# The_X_Project.net
KiCad netlist of a schematic drawn in EAGLE
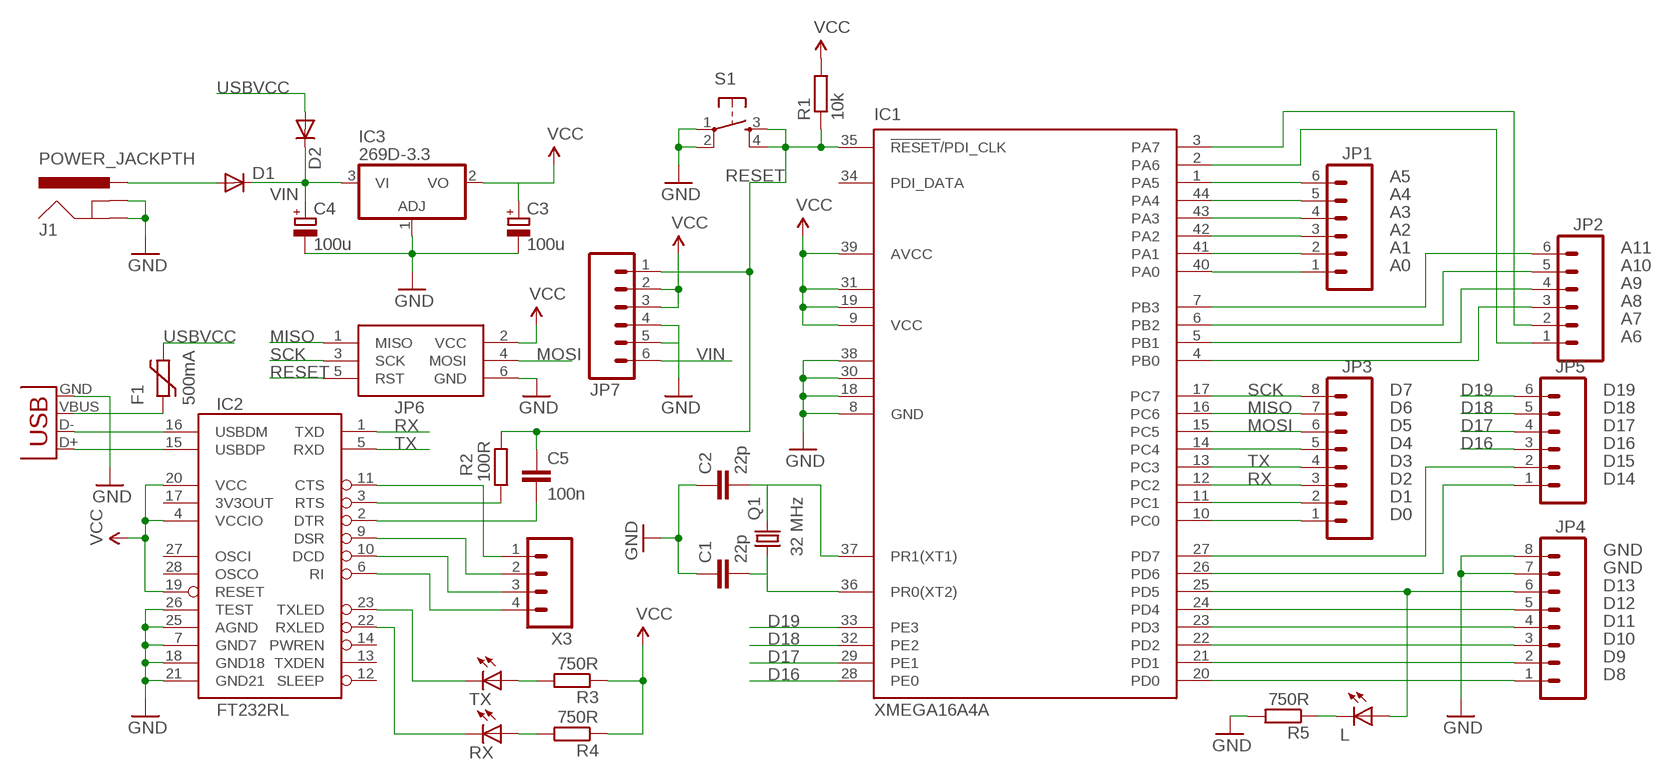
[diagram p0: schematic, sheet 1]

(export (version "E")
  (design (tool "Eeschema 10.0.6"))
  (components
    (comp (ref "C1")
      (value "22p")
      (footprint "eagle-import:C0805")
      (libsource (lib "eagle-import") (part "C-EUC0805"))
    )
    (comp (ref "C2")
      (value "22p")
      (footprint "eagle-import:C0805")
      (libsource (lib "eagle-import") (part "C-EUC0805"))
    )
    (comp (ref "C3")
      (value "100u")
      (footprint "eagle-import:PANASONIC_D")
      (libsource (lib "eagle-import") (part "CPOL-EUD"))
    )
    (comp (ref "C4")
      (value "100u")
      (footprint "eagle-import:PANASONIC_D")
      (libsource (lib "eagle-import") (part "CPOL-EUD"))
    )
    (comp (ref "C5")
      (value "100n")
      (footprint "eagle-import:C0805")
      (libsource (lib "eagle-import") (part "C-EUC0805"))
    )
    (comp (ref "D1")
      (value "DIODE-SMB")
      (footprint "eagle-import:SMB")
      (libsource (lib "eagle-import") (part "DIODE-SMB"))
    )
    (comp (ref "D2")
      (value "DIODE-SMB")
      (footprint "eagle-import:SMB")
      (libsource (lib "eagle-import") (part "DIODE-SMB"))
    )
    (comp (ref "F1")
      (value "500mA")
      (footprint "eagle-import:1812L")
      (libsource (lib "eagle-import") (part "1812L"))
    )
    (comp (ref "IC1")
      (value "XMEGA16A4A")
      (footprint "eagle-import:TQFP44")
      (libsource (lib "eagle-import") (part "XMEGA16A4A"))
    )
    (comp (ref "IC2")
      (value "FT232RL")
      (footprint "eagle-import:SSOP28DB")
      (libsource (lib "eagle-import") (part "FT232RLSSOP"))
    )
    (comp (ref "IC3")
      (value "269D-3.3")
      (footprint "eagle-import:DPACK")
      (libsource (lib "eagle-import") (part "MC33269?D-3.3"))
    )
    (comp (ref "J1")
      (value "POWER_JACKPTH")
      (footprint "eagle-import:POWER_JACK_PTH")
      (libsource (lib "eagle-import") (part "POWER_JACKPTH"))
    )
    (comp (ref "JP1")
      (value "M06SIP")
      (footprint "eagle-import:1X06")
      (libsource (lib "eagle-import") (part "M06SIP"))
    )
    (comp (ref "JP2")
      (value "M06SIP")
      (footprint "eagle-import:1X06")
      (libsource (lib "eagle-import") (part "M06SIP"))
    )
    (comp (ref "JP3")
      (value "M08")
      (footprint "eagle-import:1X08")
      (libsource (lib "eagle-import") (part "M08"))
    )
    (comp (ref "JP4")
      (value "M08")
      (footprint "eagle-import:1X08")
      (libsource (lib "eagle-import") (part "M08"))
    )
    (comp (ref "JP5")
      (value "M06SIP")
      (footprint "eagle-import:1X06")
      (libsource (lib "eagle-import") (part "M06SIP"))
    )
    (comp (ref "JP6")
      (value "AVRISP-6")
      (footprint "eagle-import:AVRISP")
      (libsource (lib "eagle-import") (part "AVRISP-6"))
    )
    (comp (ref "JP7")
      (value "M06SIP")
      (footprint "eagle-import:1X06")
      (libsource (lib "eagle-import") (part "M06SIP"))
    )
    (comp (ref "L")
      (value "LED1206")
      (footprint "eagle-import:LED-1206")
      (libsource (lib "eagle-import") (part "LED1206"))
    )
    (comp (ref "Q1")
      (value "32 MHz")
      (footprint "eagle-import:HC49U-LM")
      (libsource (lib "eagle-import") (part "CRYSTALHC49U-LM"))
    )
    (comp (ref "R1")
      (value "10k")
      (footprint "eagle-import:R0805")
      (libsource (lib "eagle-import") (part "R-EU_R0805"))
    )
    (comp (ref "R2")
      (value "100R")
      (footprint "eagle-import:R0805")
      (libsource (lib "eagle-import") (part "R-EU_R0805"))
    )
    (comp (ref "R3")
      (value "750R")
      (footprint "eagle-import:R0805")
      (libsource (lib "eagle-import") (part "R-EU_R0805"))
    )
    (comp (ref "R4")
      (value "750R")
      (footprint "eagle-import:R0805")
      (libsource (lib "eagle-import") (part "R-EU_R0805"))
    )
    (comp (ref "R5")
      (value "750R")
      (footprint "eagle-import:R0805")
      (libsource (lib "eagle-import") (part "R-EU_R0805"))
    )
    (comp (ref "RX")
      (value "LED1206")
      (footprint "eagle-import:LED-1206")
      (libsource (lib "eagle-import") (part "LED1206"))
    )
    (comp (ref "S1")
      (value "TAC_SWITCHPTH")
      (footprint "eagle-import:TACTILE-PTH")
      (libsource (lib "eagle-import") (part "TAC_SWITCHPTH"))
    )
    (comp (ref "TX")
      (value "LED1206")
      (footprint "eagle-import:LED-1206")
      (libsource (lib "eagle-import") (part "LED1206"))
    )
    (comp (ref "X1")
      (value "USBSMD")
      (footprint "eagle-import:USB-MINIB")
      (libsource (lib "eagle-import") (part "USBSMD"))
    )
    (comp (ref "X3")
      (value "M04PTH")
      (footprint "eagle-import:1X04")
      (libsource (lib "eagle-import") (part "M04PTH"))
    )
  )
  (nets
    (net (code "1") (name "/D16") (class "Default")
      (node (ref "IC1") (pin "28") (pinfunction "PE0_28") (pintype "bidirectional"))
      (node (ref "JP5") (pin "3") (pinfunction "3_3") (pintype "passive"))
    )
    (net (code "2") (name "/D17") (class "Default")
      (node (ref "IC1") (pin "29") (pinfunction "PE1_29") (pintype "bidirectional"))
      (node (ref "JP5") (pin "4") (pinfunction "4_4") (pintype "passive"))
    )
    (net (code "3") (name "/D18") (class "Default")
      (node (ref "IC1") (pin "32") (pinfunction "PE2_32") (pintype "bidirectional"))
      (node (ref "JP5") (pin "5") (pinfunction "5_5") (pintype "passive"))
    )
    (net (code "4") (name "/D19") (class "Default")
      (node (ref "IC1") (pin "33") (pinfunction "PE3_33") (pintype "bidirectional"))
      (node (ref "JP5") (pin "6") (pinfunction "6_6") (pintype "passive"))
    )
    (net (code "5") (name "/MISO") (class "Default")
      (node (ref "IC1") (pin "16") (pinfunction "PC6_16") (pintype "bidirectional"))
      (node (ref "JP3") (pin "7") (pinfunction "7_7") (pintype "passive"))
      (node (ref "JP6") (pin "1") (pinfunction "MISO_1") (pintype "input"))
    )
    (net (code "6") (name "/MOSI") (class "Default")
      (node (ref "IC1") (pin "15") (pinfunction "PC5_15") (pintype "bidirectional"))
      (node (ref "JP3") (pin "6") (pinfunction "6_6") (pintype "passive"))
      (node (ref "JP6") (pin "4") (pinfunction "MOSI_4") (pintype "output"))
    )
    (net (code "7") (name "/RESET") (class "Default")
      (node (ref "C5") (pin "1") (pinfunction "1_1") (pintype "passive"))
      (node (ref "IC1") (pin "35") (pinfunction "~{RESET}/PDI_CLK_35") (pintype "bidirectional"))
      (node (ref "JP6") (pin "5") (pinfunction "RST_5") (pintype "output"))
      (node (ref "JP7") (pin "1") (pinfunction "1_1") (pintype "passive"))
      (node (ref "R1") (pin "1") (pinfunction "1_1") (pintype "passive"))
      (node (ref "R2") (pin "2") (pinfunction "2_2") (pintype "passive"))
      (node (ref "S1") (pin "3") (pinfunction "3_3") (pintype "passive"))
      (node (ref "S1") (pin "4") (pinfunction "4_4") (pintype "passive"))
    )
    (net (code "8") (name "/RX") (class "Default")
      (node (ref "IC1") (pin "12") (pinfunction "PC2_12") (pintype "bidirectional"))
      (node (ref "IC2") (pin "1") (pinfunction "TXD_1") (pintype "output"))
      (node (ref "JP3") (pin "3") (pinfunction "3_3") (pintype "passive"))
    )
    (net (code "9") (name "/SCK") (class "Default")
      (node (ref "IC1") (pin "17") (pinfunction "PC7_17") (pintype "bidirectional"))
      (node (ref "JP3") (pin "8") (pinfunction "8_8") (pintype "passive"))
      (node (ref "JP6") (pin "3") (pinfunction "SCK_3") (pintype "output"))
    )
    (net (code "10") (name "/TX") (class "Default")
      (node (ref "IC1") (pin "13") (pinfunction "PC3_13") (pintype "bidirectional"))
      (node (ref "IC2") (pin "5") (pinfunction "RXD_5") (pintype "input"))
      (node (ref "JP3") (pin "4") (pinfunction "4_4") (pintype "passive"))
    )
    (net (code "11") (name "/USBVCC") (class "Default")
      (node (ref "D2") (pin "A") (pinfunction "A_A") (pintype "passive"))
      (node (ref "F1") (pin "P$2") (pinfunction "2_P$2") (pintype "passive"))
    )
    (net (code "12") (name "/VIN") (class "Default")
      (node (ref "C4") (pin "+") (pinfunction "+_+") (pintype "passive"))
      (node (ref "D1") (pin "C") (pinfunction "C_C") (pintype "passive"))
      (node (ref "D2") (pin "C") (pinfunction "C_C") (pintype "passive"))
      (node (ref "IC3") (pin "3") (pinfunction "VI_3") (pintype "input"))
      (node (ref "JP7") (pin "6") (pinfunction "6_6") (pintype "passive"))
    )
    (net (code "13") (name "GND") (class "Default")
      (node (ref "C1") (pin "1") (pinfunction "1_1") (pintype "passive"))
      (node (ref "C2") (pin "1") (pinfunction "1_1") (pintype "passive"))
      (node (ref "C3") (pin "-") (pinfunction "-_-") (pintype "passive"))
      (node (ref "C4") (pin "-") (pinfunction "-_-") (pintype "passive"))
      (node (ref "IC1") (pin "18") (pinfunction "GND1_18") (pintype "power_in"))
      (node (ref "IC1") (pin "30") (pinfunction "GND2_30") (pintype "power_in"))
      (node (ref "IC1") (pin "38") (pinfunction "GND3_38") (pintype "power_in"))
      (node (ref "IC1") (pin "8") (pinfunction "GND_8") (pintype "power_in"))
      (node (ref "IC2") (pin "18") (pinfunction "GND18_18") (pintype "power_in"))
      (node (ref "IC2") (pin "21") (pinfunction "GND21_21") (pintype "power_in"))
      (node (ref "IC2") (pin "25") (pinfunction "AGND_25") (pintype "power_in"))
      (node (ref "IC2") (pin "26") (pinfunction "TEST_26") (pintype "input"))
      (node (ref "IC2") (pin "7") (pinfunction "GND7_7") (pintype "power_in"))
      (node (ref "IC3") (pin "1") (pinfunction "ADJ_1") (pintype "input"))
      (node (ref "J1") (pin "GND") (pinfunction "GND_GND") (pintype "bidirectional"))
      (node (ref "J1") (pin "GNDBREAK") (pinfunction "GNDBREAK_GNDBREAK") (pintype "bidirectional"))
      (node (ref "JP4") (pin "7") (pinfunction "7_7") (pintype "passive"))
      (node (ref "JP4") (pin "8") (pinfunction "8_8") (pintype "passive"))
      (node (ref "JP6") (pin "6") (pinfunction "GND_6") (pintype "power_in"))
      (node (ref "JP7") (pin "4") (pinfunction "4_4") (pintype "passive"))
      (node (ref "JP7") (pin "5") (pinfunction "5_5") (pintype "passive"))
      (node (ref "R5") (pin "2") (pinfunction "2_2") (pintype "passive"))
      (node (ref "S1") (pin "1") (pinfunction "1_1") (pintype "passive"))
      (node (ref "S1") (pin "2") (pinfunction "2_2") (pintype "passive"))
      (node (ref "X1") (pin "GND") (pinfunction "GND_GND") (pintype "bidirectional"))
    )
    (net (code "14") (name "Net-(D1-PadA)") (class "Default")
      (node (ref "D1") (pin "A") (pinfunction "A_A") (pintype "passive"))
      (node (ref "J1") (pin "PWR") (pinfunction "PWR_PWR") (pintype "bidirectional"))
    )
    (net (code "15") (name "Net-(F1-1)") (class "Default")
      (node (ref "F1") (pin "P$1") (pinfunction "1_P$1") (pintype "passive"))
      (node (ref "X1") (pin "VBUS") (pinfunction "VBUS_VBUS") (pintype "bidirectional"))
    )
    (net (code "16") (name "Net-(IC1-PA0)") (class "Default")
      (node (ref "IC1") (pin "40") (pinfunction "PA0_40") (pintype "bidirectional"))
      (node (ref "JP1") (pin "1") (pinfunction "1_1") (pintype "passive"))
    )
    (net (code "17") (name "Net-(IC1-PA1)") (class "Default")
      (node (ref "IC1") (pin "41") (pinfunction "PA1_41") (pintype "bidirectional"))
      (node (ref "JP1") (pin "2") (pinfunction "2_2") (pintype "passive"))
    )
    (net (code "18") (name "Net-(IC1-PA2)") (class "Default")
      (node (ref "IC1") (pin "42") (pinfunction "PA2_42") (pintype "bidirectional"))
      (node (ref "JP1") (pin "3") (pinfunction "3_3") (pintype "passive"))
    )
    (net (code "19") (name "Net-(IC1-PA3)") (class "Default")
      (node (ref "IC1") (pin "43") (pinfunction "PA3_43") (pintype "bidirectional"))
      (node (ref "JP1") (pin "4") (pinfunction "4_4") (pintype "passive"))
    )
    (net (code "20") (name "Net-(IC1-PA4)") (class "Default")
      (node (ref "IC1") (pin "44") (pinfunction "PA4_44") (pintype "bidirectional"))
      (node (ref "JP1") (pin "5") (pinfunction "5_5") (pintype "passive"))
    )
    (net (code "21") (name "Net-(IC1-PA5)") (class "Default")
      (node (ref "IC1") (pin "1") (pinfunction "PA5_1") (pintype "bidirectional"))
      (node (ref "JP1") (pin "6") (pinfunction "6_6") (pintype "passive"))
    )
    (net (code "22") (name "Net-(IC1-PA6)") (class "Default")
      (node (ref "IC1") (pin "2") (pinfunction "PA6_2") (pintype "bidirectional"))
      (node (ref "JP2") (pin "1") (pinfunction "1_1") (pintype "passive"))
    )
    (net (code "23") (name "Net-(IC1-PA7)") (class "Default")
      (node (ref "IC1") (pin "3") (pinfunction "PA7_3") (pintype "bidirectional"))
      (node (ref "JP2") (pin "2") (pinfunction "2_2") (pintype "passive"))
    )
    (net (code "24") (name "Net-(IC1-PB0)") (class "Default")
      (node (ref "IC1") (pin "4") (pinfunction "PB0_4") (pintype "bidirectional"))
      (node (ref "JP2") (pin "3") (pinfunction "3_3") (pintype "passive"))
    )
    (net (code "25") (name "Net-(IC1-PB1)") (class "Default")
      (node (ref "IC1") (pin "5") (pinfunction "PB1_5") (pintype "bidirectional"))
      (node (ref "JP2") (pin "4") (pinfunction "4_4") (pintype "passive"))
    )
    (net (code "26") (name "Net-(IC1-PB2)") (class "Default")
      (node (ref "IC1") (pin "6") (pinfunction "PB2_6") (pintype "bidirectional"))
      (node (ref "JP2") (pin "5") (pinfunction "5_5") (pintype "passive"))
    )
    (net (code "27") (name "Net-(IC1-PB3)") (class "Default")
      (node (ref "IC1") (pin "7") (pinfunction "PB3_7") (pintype "bidirectional"))
      (node (ref "JP2") (pin "6") (pinfunction "6_6") (pintype "passive"))
    )
    (net (code "28") (name "Net-(IC1-PC0)") (class "Default")
      (node (ref "IC1") (pin "10") (pinfunction "PC0_10") (pintype "bidirectional"))
      (node (ref "JP3") (pin "1") (pinfunction "1_1") (pintype "passive"))
    )
    (net (code "29") (name "Net-(IC1-PC1)") (class "Default")
      (node (ref "IC1") (pin "11") (pinfunction "PC1_11") (pintype "bidirectional"))
      (node (ref "JP3") (pin "2") (pinfunction "2_2") (pintype "passive"))
    )
    (net (code "30") (name "Net-(IC1-PC4)") (class "Default")
      (node (ref "IC1") (pin "14") (pinfunction "PC4_14") (pintype "bidirectional"))
      (node (ref "JP3") (pin "5") (pinfunction "5_5") (pintype "passive"))
    )
    (net (code "31") (name "Net-(IC1-PD0)") (class "Default")
      (node (ref "IC1") (pin "20") (pinfunction "PD0_20") (pintype "bidirectional"))
      (node (ref "JP4") (pin "1") (pinfunction "1_1") (pintype "passive"))
    )
    (net (code "32") (name "Net-(IC1-PD1)") (class "Default")
      (node (ref "IC1") (pin "21") (pinfunction "PD1_21") (pintype "bidirectional"))
      (node (ref "JP4") (pin "2") (pinfunction "2_2") (pintype "passive"))
    )
    (net (code "33") (name "Net-(IC1-PD2)") (class "Default")
      (node (ref "IC1") (pin "22") (pinfunction "PD2_22") (pintype "bidirectional"))
      (node (ref "JP4") (pin "3") (pinfunction "3_3") (pintype "passive"))
    )
    (net (code "34") (name "Net-(IC1-PD3)") (class "Default")
      (node (ref "IC1") (pin "23") (pinfunction "PD3_23") (pintype "bidirectional"))
      (node (ref "JP4") (pin "4") (pinfunction "4_4") (pintype "passive"))
    )
    (net (code "35") (name "Net-(IC1-PD4)") (class "Default")
      (node (ref "IC1") (pin "24") (pinfunction "PD4_24") (pintype "bidirectional"))
      (node (ref "JP4") (pin "5") (pinfunction "5_5") (pintype "passive"))
    )
    (net (code "36") (name "Net-(IC1-PD5)") (class "Default")
      (node (ref "IC1") (pin "25") (pinfunction "PD5_25") (pintype "bidirectional"))
      (node (ref "JP4") (pin "6") (pinfunction "6_6") (pintype "passive"))
      (node (ref "L") (pin "A") (pinfunction "A_A") (pintype "passive"))
    )
    (net (code "37") (name "Net-(IC1-PD6)") (class "Default")
      (node (ref "IC1") (pin "26") (pinfunction "PD6_26") (pintype "bidirectional"))
      (node (ref "JP5") (pin "1") (pinfunction "1_1") (pintype "passive"))
    )
    (net (code "38") (name "Net-(IC1-PD7)") (class "Default")
      (node (ref "IC1") (pin "27") (pinfunction "PD7_27") (pintype "bidirectional"))
      (node (ref "JP5") (pin "2") (pinfunction "2_2") (pintype "passive"))
    )
    (net (code "39") (name "Net-(IC1-PR0(XT2))") (class "Default")
      (node (ref "C1") (pin "2") (pinfunction "2_2") (pintype "passive"))
      (node (ref "IC1") (pin "36") (pinfunction "PR0(XT2)_36") (pintype "bidirectional"))
      (node (ref "Q1") (pin "1") (pinfunction "1_1") (pintype "passive"))
    )
    (net (code "40") (name "Net-(IC1-PR1(XT1))") (class "Default")
      (node (ref "C2") (pin "2") (pinfunction "2_2") (pintype "passive"))
      (node (ref "IC1") (pin "37") (pinfunction "PR1(XT1)_37") (pintype "bidirectional"))
      (node (ref "Q1") (pin "2") (pinfunction "2_2") (pintype "passive"))
    )
    (net (code "41") (name "Net-(IC2-CTS)") (class "Default")
      (node (ref "IC2") (pin "11") (pinfunction "CTS_11") (pintype "input"))
      (node (ref "X3") (pin "1") (pinfunction "1_1") (pintype "passive"))
    )
    (net (code "42") (name "Net-(IC2-DCD)") (class "Default")
      (node (ref "IC2") (pin "10") (pinfunction "DCD_10") (pintype "input"))
      (node (ref "X3") (pin "3") (pinfunction "3_3") (pintype "passive"))
    )
    (net (code "43") (name "Net-(IC2-DSR)") (class "Default")
      (node (ref "IC2") (pin "9") (pinfunction "DSR_9") (pintype "input"))
      (node (ref "X3") (pin "2") (pinfunction "2_2") (pintype "passive"))
    )
    (net (code "44") (name "Net-(IC2-DTR)") (class "Default")
      (node (ref "C5") (pin "2") (pinfunction "2_2") (pintype "passive"))
      (node (ref "IC2") (pin "2") (pinfunction "DTR_2") (pintype "output"))
    )
    (net (code "45") (name "Net-(IC2-RI)") (class "Default")
      (node (ref "IC2") (pin "6") (pinfunction "RI_6") (pintype "input"))
      (node (ref "X3") (pin "4") (pinfunction "4_4") (pintype "passive"))
    )
    (net (code "46") (name "Net-(IC2-RTS)") (class "Default")
      (node (ref "IC2") (pin "3") (pinfunction "RTS_3") (pintype "output"))
      (node (ref "R2") (pin "1") (pinfunction "1_1") (pintype "passive"))
    )
    (net (code "47") (name "Net-(IC2-RXLED)") (class "Default")
      (node (ref "IC2") (pin "22") (pinfunction "RXLED_22") (pintype "input"))
      (node (ref "RX") (pin "C") (pinfunction "C_C") (pintype "passive"))
    )
    (net (code "48") (name "Net-(IC2-TXLED)") (class "Default")
      (node (ref "IC2") (pin "23") (pinfunction "TXLED_23") (pintype "input"))
      (node (ref "TX") (pin "C") (pinfunction "C_C") (pintype "passive"))
    )
    (net (code "49") (name "Net-(IC2-USBDM)") (class "Default")
      (node (ref "IC2") (pin "16") (pinfunction "USBDM_16") (pintype "bidirectional"))
      (node (ref "X1") (pin "D-") (pinfunction "D-_D-") (pintype "bidirectional"))
    )
    (net (code "50") (name "Net-(IC2-USBDP)") (class "Default")
      (node (ref "IC2") (pin "15") (pinfunction "USBDP_15") (pintype "bidirectional"))
      (node (ref "X1") (pin "D+") (pinfunction "D+_D+") (pintype "bidirectional"))
    )
    (net (code "51") (name "Net-(L-PadC)") (class "Default")
      (node (ref "L") (pin "C") (pinfunction "C_C") (pintype "passive"))
      (node (ref "R5") (pin "1") (pinfunction "1_1") (pintype "passive"))
    )
    (net (code "52") (name "Net-(R3-Pad2)") (class "Default")
      (node (ref "R3") (pin "2") (pinfunction "2_2") (pintype "passive"))
      (node (ref "TX") (pin "A") (pinfunction "A_A") (pintype "passive"))
    )
    (net (code "53") (name "Net-(R4-Pad2)") (class "Default")
      (node (ref "R4") (pin "2") (pinfunction "2_2") (pintype "passive"))
      (node (ref "RX") (pin "A") (pinfunction "A_A") (pintype "passive"))
    )
    (net (code "54") (name "VCC") (class "Default")
      (node (ref "C3") (pin "+") (pinfunction "+_+") (pintype "passive"))
      (node (ref "IC1") (pin "19") (pinfunction "VCC1_19") (pintype "power_in"))
      (node (ref "IC1") (pin "31") (pinfunction "VCC2_31") (pintype "power_in"))
      (node (ref "IC1") (pin "39") (pinfunction "AVCC_39") (pintype "power_in"))
      (node (ref "IC1") (pin "9") (pinfunction "VCC_9") (pintype "power_in"))
      (node (ref "IC2") (pin "19") (pinfunction "RESET_19") (pintype "input"))
      (node (ref "IC2") (pin "20") (pinfunction "VCC_20") (pintype "power_in"))
      (node (ref "IC2") (pin "4") (pinfunction "VCCIO_4") (pintype "power_in"))
      (node (ref "IC3") (pin "2") (pinfunction "VO_2") (pintype "passive"))
      (node (ref "JP6") (pin "2") (pinfunction "VCC_2") (pintype "power_in"))
      (node (ref "JP7") (pin "2") (pinfunction "2_2") (pintype "passive"))
      (node (ref "JP7") (pin "3") (pinfunction "3_3") (pintype "passive"))
      (node (ref "R1") (pin "2") (pinfunction "2_2") (pintype "passive"))
      (node (ref "R3") (pin "1") (pinfunction "1_1") (pintype "passive"))
      (node (ref "R4") (pin "1") (pinfunction "1_1") (pintype "passive"))
    )
    (net (code "55") (name "unconnected-(IC1-PDI_DATA-Pad34)") (class "Default")
      (node (ref "IC1") (pin "34") (pinfunction "PDI_DATA_34") (pintype "bidirectional"))
    )
    (net (code "56") (name "unconnected-(IC2-3V3OUT-Pad17)") (class "Default")
      (node (ref "IC2") (pin "17") (pinfunction "3V3OUT_17") (pintype "output"))
    )
    (net (code "57") (name "unconnected-(IC2-OSCI-Pad27)") (class "Default")
      (node (ref "IC2") (pin "27") (pinfunction "OSCI_27") (pintype "input"))
    )
    (net (code "58") (name "unconnected-(IC2-OSCO-Pad28)") (class "Default")
      (node (ref "IC2") (pin "28") (pinfunction "OSCO_28") (pintype "output"))
    )
    (net (code "59") (name "unconnected-(IC2-PWREN-Pad14)") (class "Default")
      (node (ref "IC2") (pin "14") (pinfunction "PWREN_14") (pintype "input"))
    )
    (net (code "60") (name "unconnected-(IC2-SLEEP-Pad12)") (class "Default")
      (node (ref "IC2") (pin "12") (pinfunction "SLEEP_12") (pintype "input"))
    )
    (net (code "61") (name "unconnected-(IC2-TXDEN-Pad13)") (class "Default")
      (node (ref "IC2") (pin "13") (pinfunction "TXDEN_13") (pintype "input"))
    )
  )
)
